# clocking.net
KiCad netlist of a schematic drawn in Altium Designer
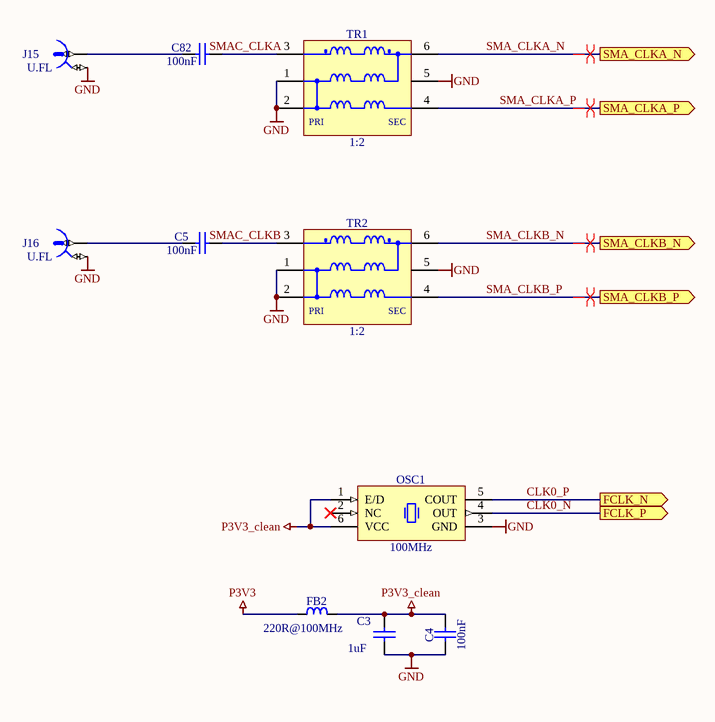
[diagram p0: clocking.SchDoc]

(export (version "E")
  (design (tool "Eeschema 10.0.6"))
  (components
    (comp (ref "C3")
      (value "1uF")
      (footprint "CAPC1608X87N")
      (description "Non-polarised capacitor")
      (fields
        (field (name "PART NUMBER") "CC0603_1UF_25V_10%_X7R")
        (field (name "VOLTAGE") "25V")
        (field (name "AUTHOR") "CERN DEM JLC")
      )
      (libsource (lib "Capacitors") (part "Capacitor - non polarized"))
    )
    (comp (ref "C4")
      (value "100nF")
      (footprint "CAPC1005X55N")
      (description "Non-polarised capacitor")
      (fields
        (field (name "PART NUMBER") "CC0402_100NF_16V_10%_X5R")
        (field (name "VOLTAGE") "16V")
        (field (name "AUTHOR") "CERN DEM JLC")
      )
      (libsource (lib "Capacitors") (part "Capacitor - non polarized"))
    )
    (comp (ref "C5")
      (value "100nF")
      (footprint "CAPC1005X55N")
      (description "Non-polarised capacitor")
      (fields
        (field (name "PART NUMBER") "CC0402_100NF_16V_10%_X5R")
        (field (name "VOLTAGE") "16V")
        (field (name "AUTHOR") "CERN DEM JLC")
      )
      (libsource (lib "Capacitors") (part "Capacitor - non polarized"))
    )
    (comp (ref "C82")
      (value "100nF")
      (footprint "CAPC1005X55N")
      (description "Non-polarised capacitor")
      (fields
        (field (name "PART NUMBER") "CC0402_100NF_16V_10%_X5R")
        (field (name "VOLTAGE") "16V")
        (field (name "AUTHOR") "CERN DEM JLC")
      )
      (libsource (lib "Capacitors") (part "Capacitor - non polarized"))
    )
    (comp (ref "FB2")
      (value "220R@100MHz")
      (footprint "INDC2012X105N")
      (description "Inductor")
      (fields
        (field (name "PART NUMBER") "IND0805_MURATA_BLM21PG221SN1D")
        (field (name "POWER") "2A")
        (field (name "AUTHOR") "CERN DEM JLC")
      )
      (libsource (lib "Inductors & Transformers") (part "Inductor"))
    )
    (comp (ref "J15")
      (value "U.FL")
      (footprint "HIROSE_U.FL-R-SMT-1(10)")
      (fields
        (field (name "PART NUMBER") "HIROSE_U.FL-R-SMT-1(10)")
        (field (name "MANUFACTURER") "HIROSE (HRS)")
        (field (name "MANUFACTURER PART NUMBER") "U.FL-R-SMT-1(10)")
        (field (name "AUTHOR") "CERN DEM JLC")
      )
      (libsource (lib "Connectors") (part "Coax_1Male_1Shield"))
    )
    (comp (ref "J16")
      (value "U.FL")
      (footprint "HIROSE_U.FL-R-SMT-1(10)")
      (fields
        (field (name "PART NUMBER") "HIROSE_U.FL-R-SMT-1(10)")
        (field (name "MANUFACTURER") "HIROSE (HRS)")
        (field (name "MANUFACTURER PART NUMBER") "U.FL-R-SMT-1(10)")
        (field (name "AUTHOR") "CERN DEM JLC")
      )
      (libsource (lib "Connectors") (part "Coax_1Male_1Shield"))
    )
    (comp (ref "OSC1")
      (value "100MHz")
      (footprint "OSC_CRYSTEK_CCLD-033")
      (description "3.3V, ± 50ppm, 0°C to +70°C, Surface Mount LVDS Clock Oscillator (CCLD-033 Series)")
      (fields
        (field (name "PART NUMBER") "OSC_100MHZ_CRYSTEK_CCLD-033-50-100.000")
        (field (name "MANUFACTURER") "CRYSTEK CRYSTAL")
        (field (name "AUTHOR") "CERN DEM JLC")
      )
      (libsource (lib "ICs And Semiconductors") (part "OSC_CRYSTEK_CCLD-033"))
    )
    (comp (ref "TR1")
      (value "1:2")
      (footprint "XFMR_MINI-CIRCUITS_DB1627")
      (description "50 OHMS 10 to 4000 MHz RF Transformer")
      (fields
        (field (name "PART NUMBER") "XFMR_MINI-CIRCUITS_TCM2-43X+")
        (field (name "POWER") "0.4W")
        (field (name "AUTHOR") "CERN DEM BC")
      )
      (libsource (lib "Inductors & Transformers") (part "XFMR_MINI-CIRCUITS_TCM2-43X"))
    )
    (comp (ref "TR2")
      (value "1:2")
      (footprint "XFMR_MINI-CIRCUITS_DB1627")
      (description "50 OHMS 10 to 4000 MHz RF Transformer")
      (fields
        (field (name "PART NUMBER") "XFMR_MINI-CIRCUITS_TCM2-43X+")
        (field (name "POWER") "0.4W")
        (field (name "AUTHOR") "CERN DEM BC")
      )
      (libsource (lib "Inductors & Transformers") (part "XFMR_MINI-CIRCUITS_TCM2-43X"))
    )
  )
  (nets
    (net (code "1") (name "/CLK0_N") (class "Default")
      (node (ref "OSC1") (pin "4") (pinfunction "OUT_4") (pintype "output"))
    )
    (net (code "2") (name "/CLK0_P") (class "Default")
      (node (ref "OSC1") (pin "5") (pinfunction "COUT_5") (pintype "passive"))
    )
    (net (code "5") (name "/SMA_CLKA_N") (class "Default")
      (node (ref "TR1") (pin "6") (pinfunction "S1_6") (pintype "passive"))
    )
    (net (code "6") (name "/SMA_CLKA_P") (class "Default")
      (node (ref "TR1") (pin "4") (pinfunction "S1_4") (pintype "passive"))
    )
    (net (code "7") (name "/SMA_CLKB_N") (class "Default")
      (node (ref "TR2") (pin "6") (pinfunction "S1_6") (pintype "passive"))
    )
    (net (code "8") (name "/SMA_CLKB_P") (class "Default")
      (node (ref "TR2") (pin "4") (pinfunction "S1_4") (pintype "passive"))
    )
    (net (code "9") (name "GND") (class "Default")
      (node (ref "C3") (pin "1") (pinfunction "1_1") (pintype "passive"))
      (node (ref "C4") (pin "1") (pinfunction "1_1") (pintype "passive"))
      (node (ref "J15") (pin "2") (pinfunction "2_2") (pintype "bidirectional"))
      (node (ref "J16") (pin "2") (pinfunction "2_2") (pintype "bidirectional"))
      (node (ref "OSC1") (pin "3") (pinfunction "GND_3") (pintype "power_in"))
      (node (ref "TR1") (pin "1") (pinfunction "P1_1") (pintype "passive"))
      (node (ref "TR1") (pin "2") (pinfunction "P1_2") (pintype "passive"))
      (node (ref "TR1") (pin "5") (pinfunction "NC_5") (pintype "passive"))
      (node (ref "TR2") (pin "1") (pinfunction "P1_1") (pintype "passive"))
      (node (ref "TR2") (pin "2") (pinfunction "P1_2") (pintype "passive"))
      (node (ref "TR2") (pin "5") (pinfunction "NC_5") (pintype "passive"))
    )
    (net (code "10") (name "Net-(C5-Pad1)") (class "Default")
      (node (ref "C5") (pin "1") (pinfunction "1_1") (pintype "passive"))
      (node (ref "TR2") (pin "3") (pinfunction "P1_3") (pintype "passive"))
    )
    (net (code "11") (name "Net-(C5-Pad2)") (class "Default")
      (node (ref "C5") (pin "2") (pinfunction "2_2") (pintype "passive"))
      (node (ref "J16") (pin "1") (pinfunction "1_1") (pintype "bidirectional"))
    )
    (net (code "12") (name "Net-(C82-Pad1)") (class "Default")
      (node (ref "C82") (pin "1") (pinfunction "1_1") (pintype "passive"))
      (node (ref "TR1") (pin "3") (pinfunction "P1_3") (pintype "passive"))
    )
    (net (code "13") (name "Net-(C82-Pad2)") (class "Default")
      (node (ref "C82") (pin "2") (pinfunction "2_2") (pintype "passive"))
      (node (ref "J15") (pin "1") (pinfunction "1_1") (pintype "bidirectional"))
    )
    (net (code "14") (name "P3V3") (class "Default")
      (node (ref "FB2") (pin "1") (pinfunction "1_1") (pintype "passive"))
    )
    (net (code "15") (name "P3V3_clean") (class "Default")
      (node (ref "C3") (pin "2") (pinfunction "2_2") (pintype "passive"))
      (node (ref "C4") (pin "2") (pinfunction "2_2") (pintype "passive"))
      (node (ref "FB2") (pin "2") (pinfunction "2_2") (pintype "passive"))
      (node (ref "OSC1") (pin "1") (pinfunction "E/D_1") (pintype "input"))
      (node (ref "OSC1") (pin "6") (pinfunction "VCC_6") (pintype "power_in"))
    )
    (net (code "16") (name "unconnected-(OSC1-NC-Pad2)") (class "Default")
      (node (ref "OSC1") (pin "2") (pinfunction "NC_2") (pintype "input+no_connect"))
    )
  )
)
